# LTE.net
KiCad netlist of a schematic drawn in Altium Designer
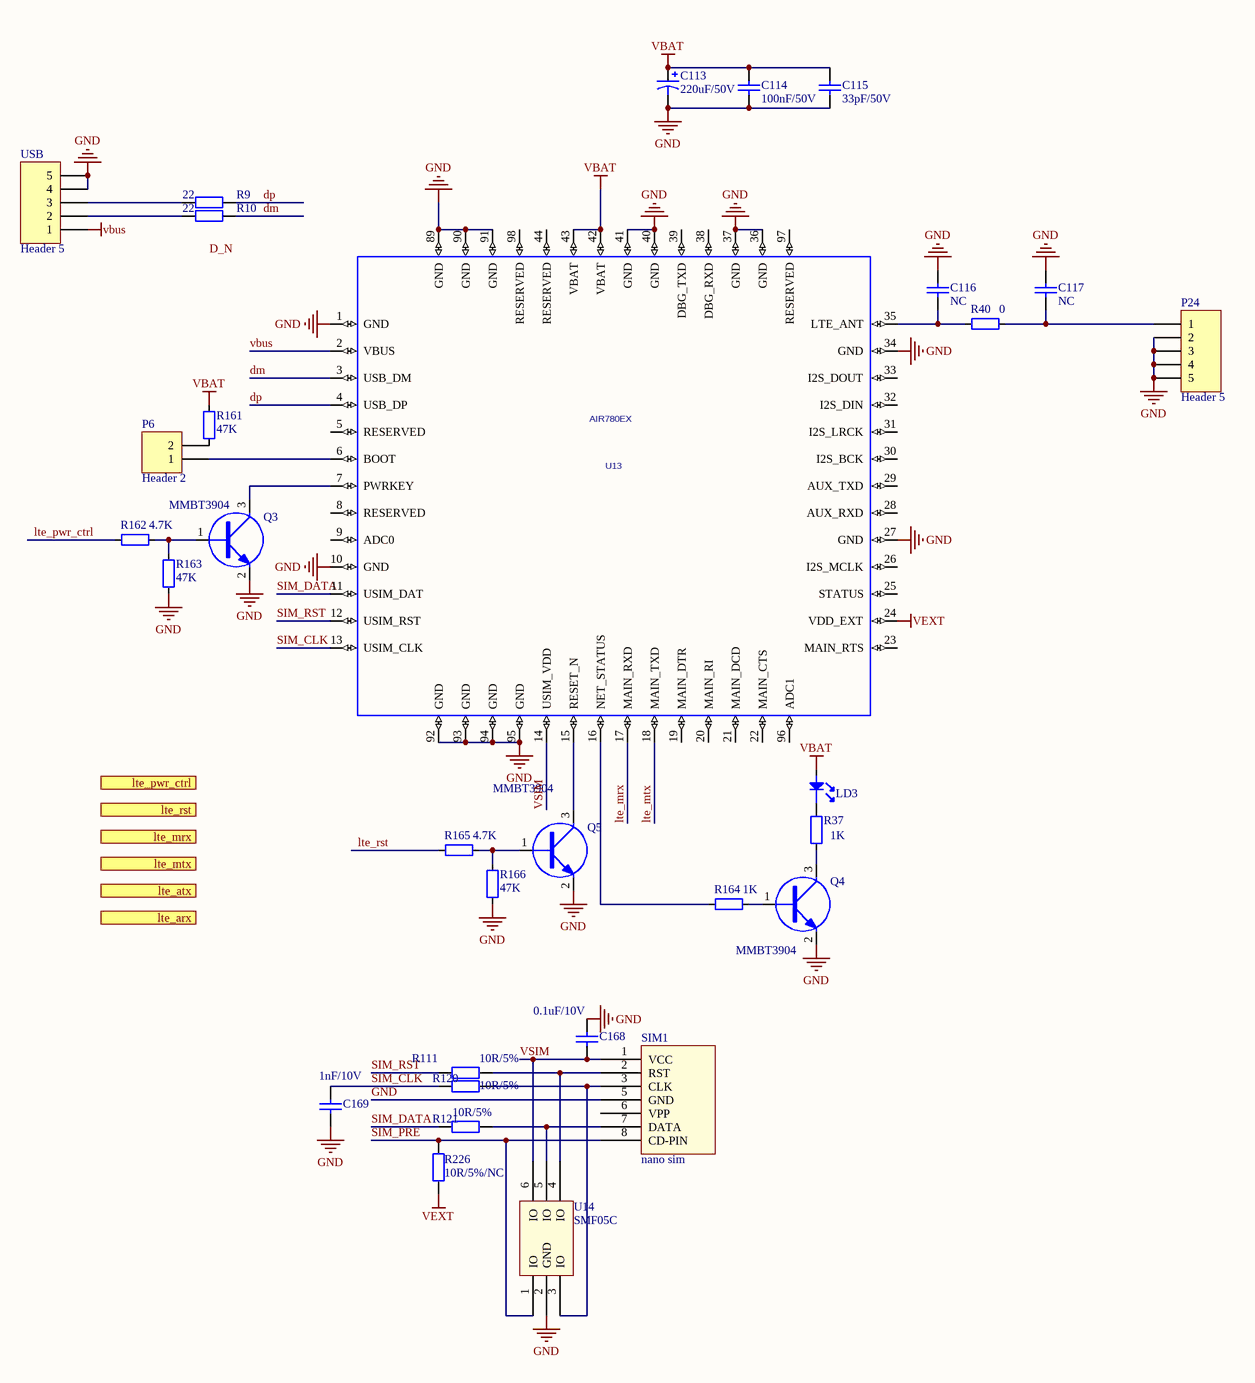
[diagram p0: LTE.SchDoc]

(export (version "E")
  (design (tool "Eeschema 10.0.6"))
  (components
    (comp (ref "C113")
      (value "220uF/50V")
      (footprint "Φ10×10")
      (description "Polarized Capacitor (Radial)")
      (fields (field (name "PUBLISHER") "Altium Limited"))
      (libsource (lib "Miscellaneous Devices") (part "Cap Pol1"))
    )
    (comp (ref "C114")
      (value "100nF/50V")
      (footprint "0603C")
      (description "Capacitor")
      (fields (field (name "PUBLISHER") "Altium Limited"))
      (libsource (lib "Miscellaneous Devices") (part "Cap"))
    )
    (comp (ref "C115")
      (value "33pF/50V")
      (footprint "0603C")
      (description "Capacitor")
      (fields (field (name "PUBLISHER") "Altium Limited"))
      (libsource (lib "Miscellaneous Devices") (part "Cap"))
    )
    (comp (ref "C116")
      (value "NC")
      (footprint "0603c")
      (description "Capacitor")
      (fields (field (name "PUBLISHER") "Altium Limited"))
      (libsource (lib "Miscellaneous Devices") (part "Cap"))
    )
    (comp (ref "C117")
      (value "NC")
      (footprint "0603c")
      (description "Capacitor")
      (fields (field (name "PUBLISHER") "Altium Limited"))
      (libsource (lib "Miscellaneous Devices") (part "Cap"))
    )
    (comp (ref "C168")
      (value "0.1uF/10V")
      (footprint "0603c")
      (description "Capacitor")
      (fields (field (name "PUBLISHER") "Altium Limited"))
      (libsource (lib "Miscellaneous Devices") (part "Cap"))
    )
    (comp (ref "C169")
      (value "1nF/10V")
      (footprint "0603c")
      (description "Capacitor")
      (fields (field (name "PUBLISHER") "Altium Limited"))
      (libsource (lib "Miscellaneous Devices") (part "Cap"))
    )
    (comp (ref "LD3")
      (value "LED_Green_19-217")
      (footprint "0603led")
      (libsource (lib "RC_M_D_00") (part "LED_Green_19-217"))
    )
    (comp (ref "P6")
      (value "Header 2")
      (footprint "HDR1X2")
      (description "Header, 2-Pin")
      (fields (field (name "PUBLISHER") "Altium Limited"))
      (libsource (lib "Miscellaneous Connectors") (part "Header 2"))
    )
    (comp (ref "P24")
      (value "Header 5")
      (footprint "KH-SMA-KE-Z")
      (description "Header, 5-Pin")
      (fields (field (name "PUBLISHER") "Altium Limited"))
      (libsource (lib "Miscellaneous Connectors") (part "Header 5"))
    )
    (comp (ref "Q3")
      (value "MMBT3904")
      (footprint "SOT23-3")
      (libsource (lib "CenLib") (part "NPN_MMBT3904"))
    )
    (comp (ref "Q4")
      (value "MMBT3904")
      (footprint "SOT23-3")
      (libsource (lib "CenLib") (part "NPN_MMBT3904"))
    )
    (comp (ref "Q5")
      (value "MMBT3904")
      (footprint "SOT23-3")
      (libsource (lib "CenLib") (part "NPN_MMBT3904"))
    )
    (comp (ref "R9")
      (value "22")
      (footprint "0402R")
      (description "Resistor SMD - IEC symbol version")
      (libsource (lib "SX1276_e266v02a") (part "Resistor"))
    )
    (comp (ref "R10")
      (value "22")
      (footprint "0402R")
      (description "Resistor SMD - IEC symbol version")
      (libsource (lib "SX1276_e266v02a") (part "Resistor"))
    )
    (comp (ref "R37") (value "1K") (footprint "0603R") (libsource (lib "RC_M_D_00") (part "RES0603")))
    (comp (ref "R40") (value "0") (footprint "0603r") (libsource (lib "RC_M_D_00") (part "RES0603")))
    (comp (ref "R111")
      (value "10R/5%")
      (footprint "0603r")
      (description "Resistor")
      (fields (field (name "PUBLISHER") "Altium Limited"))
      (libsource (lib "Miscellaneous Devices") (part "Res2"))
    )
    (comp (ref "R120")
      (value "10R/5%")
      (footprint "0603r")
      (description "Resistor")
      (fields (field (name "PUBLISHER") "Altium Limited"))
      (libsource (lib "Miscellaneous Devices") (part "Res2"))
    )
    (comp (ref "R121")
      (value "10R/5%")
      (footprint "0603r")
      (description "Resistor")
      (fields (field (name "PUBLISHER") "Altium Limited"))
      (libsource (lib "Miscellaneous Devices") (part "Res2"))
    )
    (comp (ref "R161") (value "47K") (footprint "0603r") (libsource (lib "RC_M_D_00") (part "RES0603")))
    (comp (ref "R162") (value "4.7K") (footprint "0603R") (libsource (lib "RC_M_D_00") (part "RES0603")))
    (comp (ref "R163") (value "47K") (footprint "0603r") (libsource (lib "RC_M_D_00") (part "RES0603")))
    (comp (ref "R164") (value "1K") (footprint "0603r") (libsource (lib "RC_M_D_00") (part "RES0603")))
    (comp (ref "R165") (value "4.7K") (footprint "0603R") (libsource (lib "RC_M_D_00") (part "RES0603")))
    (comp (ref "R166") (value "47K") (footprint "0603r") (libsource (lib "RC_M_D_00") (part "RES0603")))
    (comp (ref "R226")
      (value "10R/5%/NC")
      (footprint "0603r")
      (description "Resistor")
      (fields (field (name "PUBLISHER") "Altium Limited"))
      (libsource (lib "") (part "Res2_1"))
    )
    (comp (ref "SIM1") (value "nano sim") (footprint "Nano SIM") (libsource (lib "lm") (part "nano sim")))
    (comp (ref "U13")
      (value "AIR780EX")
      (footprint "Air780EX_AD:AIR780EX")
      (libsource (lib "*") (part "AIR780EX"))
    )
    (comp (ref "U14") (value "SMF05C") (footprint "sc70-6l") (libsource (lib "lm") (part "SMF05C")))
    (comp (ref "USB")
      (value "Header 5")
      (footprint "USB-MICRO-5P")
      (description "Header, 5-Pin")
      (fields (field (name "PUBLISHER") "Altium Limited"))
      (libsource (lib "") (part "Header 5_1"))
    )
  )
  (nets
    (net (code "2") (name "/SIM_CLK") (class "Default")
      (node (ref "C169") (pin "1") (pinfunction "1_1") (pintype "passive"))
      (node (ref "R120") (pin "2") (pinfunction "2_2") (pintype "passive"))
      (node (ref "U13") (pin "13") (pinfunction "USIM_CLK_13") (pintype "bidirectional"))
    )
    (net (code "3") (name "/SIM_DATA") (class "Default")
      (node (ref "R121") (pin "2") (pinfunction "2_2") (pintype "passive"))
      (node (ref "U13") (pin "11") (pinfunction "USIM_DAT_11") (pintype "bidirectional"))
    )
    (net (code "4") (name "/SIM_PRE") (class "Default")
      (node (ref "R226") (pin "1") (pinfunction "1_1") (pintype "passive"))
      (node (ref "SIM1") (pin "8") (pinfunction "CD-PIN_8") (pintype "passive"))
      (node (ref "U14") (pin "1") (pinfunction "IO_1") (pintype "passive"))
    )
    (net (code "5") (name "/SIM_RST") (class "Default")
      (node (ref "R111") (pin "2") (pinfunction "2_2") (pintype "passive"))
      (node (ref "U13") (pin "12") (pinfunction "USIM_RST_12") (pintype "bidirectional"))
    )
    (net (code "6") (name "/VSIM") (class "Default")
      (node (ref "C168") (pin "2") (pinfunction "2_2") (pintype "passive"))
      (node (ref "SIM1") (pin "1") (pinfunction "VCC_1") (pintype "passive"))
      (node (ref "U13") (pin "14") (pinfunction "USIM_VDD_14") (pintype "bidirectional"))
      (node (ref "U14") (pin "6") (pinfunction "IO_6") (pintype "passive"))
    )
    (net (code "7") (name "/dm") (class "Default")
      (node (ref "R10") (pin "2") (pinfunction "2_2") (pintype "passive"))
      (node (ref "U13") (pin "3") (pinfunction "USB_DM_3") (pintype "bidirectional"))
    )
    (net (code "8") (name "/dp") (class "Default")
      (node (ref "R9") (pin "2") (pinfunction "2_2") (pintype "passive"))
      (node (ref "U13") (pin "4") (pinfunction "USB_DP_4") (pintype "bidirectional"))
    )
    (net (code "11") (name "/lte_mrx") (class "Default")
      (node (ref "U13") (pin "17") (pinfunction "MAIN_RXD_17") (pintype "bidirectional"))
    )
    (net (code "12") (name "/lte_mtx") (class "Default")
      (node (ref "U13") (pin "18") (pinfunction "MAIN_TXD_18") (pintype "bidirectional"))
    )
    (net (code "13") (name "/lte_pwr_ctrl") (class "Default")
      (node (ref "R162") (pin "1") (pinfunction "1_1") (pintype "passive"))
    )
    (net (code "14") (name "/lte_rst") (class "Default")
      (node (ref "R165") (pin "1") (pinfunction "1_1") (pintype "passive"))
    )
    (net (code "15") (name "GND") (class "Default")
      (node (ref "C113") (pin "2") (pinfunction "2_2") (pintype "passive"))
      (node (ref "C114") (pin "1") (pinfunction "1_1") (pintype "passive"))
      (node (ref "C115") (pin "1") (pinfunction "1_1") (pintype "passive"))
      (node (ref "C116") (pin "2") (pinfunction "2_2") (pintype "passive"))
      (node (ref "C117") (pin "2") (pinfunction "2_2") (pintype "passive"))
      (node (ref "C168") (pin "1") (pinfunction "1_1") (pintype "passive"))
      (node (ref "C169") (pin "2") (pinfunction "2_2") (pintype "passive"))
      (node (ref "P24") (pin "2") (pinfunction "2_2") (pintype "passive"))
      (node (ref "P24") (pin "3") (pinfunction "3_3") (pintype "passive"))
      (node (ref "P24") (pin "4") (pinfunction "4_4") (pintype "passive"))
      (node (ref "P24") (pin "5") (pinfunction "5_5") (pintype "passive"))
      (node (ref "Q3") (pin "2") (pinfunction "E_2") (pintype "passive"))
      (node (ref "Q4") (pin "2") (pinfunction "E_2") (pintype "passive"))
      (node (ref "Q5") (pin "2") (pinfunction "E_2") (pintype "passive"))
      (node (ref "R163") (pin "1") (pinfunction "1_1") (pintype "passive"))
      (node (ref "R166") (pin "1") (pinfunction "1_1") (pintype "passive"))
      (node (ref "SIM1") (pin "5") (pinfunction "GND_5") (pintype "passive"))
      (node (ref "U13") (pin "1") (pinfunction "GND_1") (pintype "bidirectional"))
      (node (ref "U13") (pin "10") (pinfunction "GND_10") (pintype "bidirectional"))
      (node (ref "U13") (pin "27") (pinfunction "GND_27") (pintype "bidirectional"))
      (node (ref "U13") (pin "34") (pinfunction "GND_34") (pintype "bidirectional"))
      (node (ref "U13") (pin "36") (pinfunction "GND_36") (pintype "bidirectional"))
      (node (ref "U13") (pin "37") (pinfunction "GND_37") (pintype "bidirectional"))
      (node (ref "U13") (pin "40") (pinfunction "GND_40") (pintype "bidirectional"))
      (node (ref "U13") (pin "41") (pinfunction "GND_41") (pintype "bidirectional"))
      (node (ref "U13") (pin "89") (pinfunction "GND_89") (pintype "bidirectional"))
      (node (ref "U13") (pin "90") (pinfunction "GND_90") (pintype "bidirectional"))
      (node (ref "U13") (pin "91") (pinfunction "GND_91") (pintype "bidirectional"))
      (node (ref "U13") (pin "92") (pinfunction "GND_92") (pintype "bidirectional"))
      (node (ref "U13") (pin "93") (pinfunction "GND_93") (pintype "bidirectional"))
      (node (ref "U13") (pin "94") (pinfunction "GND_94") (pintype "bidirectional"))
      (node (ref "U13") (pin "95") (pinfunction "GND_95") (pintype "bidirectional"))
      (node (ref "U14") (pin "2") (pinfunction "GND_2") (pintype "passive"))
      (node (ref "USB") (pin "4") (pinfunction "4_4") (pintype "passive"))
      (node (ref "USB") (pin "5") (pinfunction "5_5") (pintype "passive"))
    )
    (net (code "16") (name "Net-(C117-Pad1)") (class "Default")
      (node (ref "C117") (pin "1") (pinfunction "1_1") (pintype "passive"))
      (node (ref "P24") (pin "1") (pinfunction "1_1") (pintype "passive"))
      (node (ref "R40") (pin "2") (pinfunction "2_2") (pintype "passive"))
    )
    (net (code "17") (name "Net-(LD3-Pad2)") (class "Default")
      (node (ref "LD3") (pin "2") (pinfunction "2_2") (pintype "passive"))
      (node (ref "R37") (pin "1") (pinfunction "1_1") (pintype "passive"))
    )
    (net (code "18") (name "Net-(P6-Pad2)") (class "Default")
      (node (ref "P6") (pin "2") (pinfunction "2_2") (pintype "passive"))
      (node (ref "R161") (pin "1") (pinfunction "1_1") (pintype "passive"))
    )
    (net (code "19") (name "Net-(Q3-B)") (class "Default")
      (node (ref "Q3") (pin "1") (pinfunction "B_1") (pintype "passive"))
      (node (ref "R162") (pin "2") (pinfunction "2_2") (pintype "passive"))
      (node (ref "R163") (pin "2") (pinfunction "2_2") (pintype "passive"))
    )
    (net (code "20") (name "Net-(Q3-C)") (class "Default")
      (node (ref "Q3") (pin "3") (pinfunction "C_3") (pintype "passive"))
      (node (ref "U13") (pin "7") (pinfunction "PWRKEY_7") (pintype "bidirectional"))
    )
    (net (code "21") (name "Net-(Q4-B)") (class "Default")
      (node (ref "Q4") (pin "1") (pinfunction "B_1") (pintype "passive"))
      (node (ref "R164") (pin "2") (pinfunction "2_2") (pintype "passive"))
    )
    (net (code "22") (name "Net-(Q4-C)") (class "Default")
      (node (ref "Q4") (pin "3") (pinfunction "C_3") (pintype "passive"))
      (node (ref "R37") (pin "2") (pinfunction "2_2") (pintype "passive"))
    )
    (net (code "23") (name "Net-(Q5-B)") (class "Default")
      (node (ref "Q5") (pin "1") (pinfunction "B_1") (pintype "passive"))
      (node (ref "R165") (pin "2") (pinfunction "2_2") (pintype "passive"))
      (node (ref "R166") (pin "2") (pinfunction "2_2") (pintype "passive"))
    )
    (net (code "24") (name "Net-(Q5-C)") (class "Default")
      (node (ref "Q5") (pin "3") (pinfunction "C_3") (pintype "passive"))
      (node (ref "U13") (pin "15") (pinfunction "RESET_N_15") (pintype "bidirectional"))
    )
    (net (code "25") (name "Net-(R9-Pad1)") (class "Default")
      (node (ref "R9") (pin "1") (pinfunction "1_1") (pintype "passive"))
      (node (ref "USB") (pin "3") (pinfunction "3_3") (pintype "passive"))
    )
    (net (code "26") (name "Net-(R10-Pad1)") (class "Default")
      (node (ref "R10") (pin "1") (pinfunction "1_1") (pintype "passive"))
      (node (ref "USB") (pin "2") (pinfunction "2_2") (pintype "passive"))
    )
    (net (code "27") (name "Net-(SIM1-CLK)") (class "Default")
      (node (ref "R120") (pin "1") (pinfunction "1_1") (pintype "passive"))
      (node (ref "SIM1") (pin "3") (pinfunction "CLK_3") (pintype "passive"))
      (node (ref "U14") (pin "3") (pinfunction "IO_3") (pintype "passive"))
    )
    (net (code "28") (name "Net-(SIM1-DATA)") (class "Default")
      (node (ref "R121") (pin "1") (pinfunction "1_1") (pintype "passive"))
      (node (ref "SIM1") (pin "7") (pinfunction "DATA_7") (pintype "passive"))
      (node (ref "U14") (pin "5") (pinfunction "IO_5") (pintype "passive"))
    )
    (net (code "29") (name "Net-(SIM1-RST)") (class "Default")
      (node (ref "R111") (pin "1") (pinfunction "1_1") (pintype "passive"))
      (node (ref "SIM1") (pin "2") (pinfunction "RST_2") (pintype "passive"))
      (node (ref "U14") (pin "4") (pinfunction "IO_4") (pintype "passive"))
    )
    (net (code "30") (name "Net-(U13-BOOT)") (class "Default")
      (node (ref "P6") (pin "1") (pinfunction "1_1") (pintype "passive"))
      (node (ref "U13") (pin "6") (pinfunction "BOOT_6") (pintype "bidirectional"))
    )
    (net (code "31") (name "Net-(U13-LTE_ANT)") (class "Default")
      (node (ref "C116") (pin "1") (pinfunction "1_1") (pintype "passive"))
      (node (ref "R40") (pin "1") (pinfunction "1_1") (pintype "passive"))
      (node (ref "U13") (pin "35") (pinfunction "LTE_ANT_35") (pintype "bidirectional"))
    )
    (net (code "32") (name "Net-(U13-NET_STATUS)") (class "Default")
      (node (ref "R164") (pin "1") (pinfunction "1_1") (pintype "passive"))
      (node (ref "U13") (pin "16") (pinfunction "NET_STATUS_16") (pintype "bidirectional"))
    )
    (net (code "33") (name "VBAT") (class "Default")
      (node (ref "C113") (pin "1") (pinfunction "1_1") (pintype "passive"))
      (node (ref "C114") (pin "2") (pinfunction "2_2") (pintype "passive"))
      (node (ref "C115") (pin "2") (pinfunction "2_2") (pintype "passive"))
      (node (ref "LD3") (pin "1") (pinfunction "1_1") (pintype "passive"))
      (node (ref "R161") (pin "2") (pinfunction "2_2") (pintype "passive"))
      (node (ref "U13") (pin "42") (pinfunction "VBAT_42") (pintype "bidirectional"))
      (node (ref "U13") (pin "43") (pinfunction "VBAT_43") (pintype "bidirectional"))
    )
    (net (code "34") (name "VEXT") (class "Default")
      (node (ref "R226") (pin "2") (pinfunction "2_2") (pintype "passive"))
      (node (ref "U13") (pin "24") (pinfunction "VDD_EXT_24") (pintype "bidirectional"))
    )
    (net (code "35") (name "unconnected-(SIM1-VPP-Pad6)") (class "Default")
      (node (ref "SIM1") (pin "6") (pinfunction "VPP_6") (pintype "passive"))
    )
    (net (code "36") (name "unconnected-(U13-ADC0-Pad9)") (class "Default")
      (node (ref "U13") (pin "9") (pinfunction "ADC0_9") (pintype "bidirectional"))
    )
    (net (code "37") (name "unconnected-(U13-ADC1-Pad96)") (class "Default")
      (node (ref "U13") (pin "96") (pinfunction "ADC1_96") (pintype "bidirectional"))
    )
    (net (code "38") (name "unconnected-(U13-AUX_RXD-Pad28)") (class "Default")
      (node (ref "U13") (pin "28") (pinfunction "AUX_RXD_28") (pintype "bidirectional"))
    )
    (net (code "39") (name "unconnected-(U13-AUX_TXD-Pad29)") (class "Default")
      (node (ref "U13") (pin "29") (pinfunction "AUX_TXD_29") (pintype "bidirectional"))
    )
    (net (code "40") (name "unconnected-(U13-DBG_RXD-Pad38)") (class "Default")
      (node (ref "U13") (pin "38") (pinfunction "DBG_RXD_38") (pintype "bidirectional"))
    )
    (net (code "41") (name "unconnected-(U13-DBG_TXD-Pad39)") (class "Default")
      (node (ref "U13") (pin "39") (pinfunction "DBG_TXD_39") (pintype "bidirectional"))
    )
    (net (code "42") (name "unconnected-(U13-I2S_BCK-Pad30)") (class "Default")
      (node (ref "U13") (pin "30") (pinfunction "I2S_BCK_30") (pintype "bidirectional"))
    )
    (net (code "43") (name "unconnected-(U13-I2S_DIN-Pad32)") (class "Default")
      (node (ref "U13") (pin "32") (pinfunction "I2S_DIN_32") (pintype "bidirectional"))
    )
    (net (code "44") (name "unconnected-(U13-I2S_DOUT-Pad33)") (class "Default")
      (node (ref "U13") (pin "33") (pinfunction "I2S_DOUT_33") (pintype "bidirectional"))
    )
    (net (code "45") (name "unconnected-(U13-I2S_LRCK-Pad31)") (class "Default")
      (node (ref "U13") (pin "31") (pinfunction "I2S_LRCK_31") (pintype "bidirectional"))
    )
    (net (code "46") (name "unconnected-(U13-I2S_MCLK-Pad26)") (class "Default")
      (node (ref "U13") (pin "26") (pinfunction "I2S_MCLK_26") (pintype "bidirectional"))
    )
    (net (code "47") (name "unconnected-(U13-MAIN_CTS-Pad22)") (class "Default")
      (node (ref "U13") (pin "22") (pinfunction "MAIN_CTS_22") (pintype "bidirectional"))
    )
    (net (code "48") (name "unconnected-(U13-MAIN_DCD-Pad21)") (class "Default")
      (node (ref "U13") (pin "21") (pinfunction "MAIN_DCD_21") (pintype "bidirectional"))
    )
    (net (code "49") (name "unconnected-(U13-MAIN_DTR-Pad19)") (class "Default")
      (node (ref "U13") (pin "19") (pinfunction "MAIN_DTR_19") (pintype "bidirectional"))
    )
    (net (code "50") (name "unconnected-(U13-MAIN_RI-Pad20)") (class "Default")
      (node (ref "U13") (pin "20") (pinfunction "MAIN_RI_20") (pintype "bidirectional"))
    )
    (net (code "51") (name "unconnected-(U13-MAIN_RTS-Pad23)") (class "Default")
      (node (ref "U13") (pin "23") (pinfunction "MAIN_RTS_23") (pintype "bidirectional"))
    )
    (net (code "52") (name "unconnected-(U13-RESERVED-Pad5)") (class "Default")
      (node (ref "U13") (pin "5") (pinfunction "RESERVED_5") (pintype "bidirectional"))
    )
    (net (code "53") (name "unconnected-(U13-RESERVED-Pad8)") (class "Default")
      (node (ref "U13") (pin "8") (pinfunction "RESERVED_8") (pintype "bidirectional"))
    )
    (net (code "54") (name "unconnected-(U13-RESERVED-Pad44)") (class "Default")
      (node (ref "U13") (pin "44") (pinfunction "RESERVED_44") (pintype "bidirectional"))
    )
    (net (code "55") (name "unconnected-(U13-RESERVED-Pad97)") (class "Default")
      (node (ref "U13") (pin "97") (pinfunction "RESERVED_97") (pintype "bidirectional"))
    )
    (net (code "56") (name "unconnected-(U13-RESERVED-Pad98)") (class "Default")
      (node (ref "U13") (pin "98") (pinfunction "RESERVED_98") (pintype "bidirectional"))
    )
    (net (code "57") (name "unconnected-(U13-STATUS-Pad25)") (class "Default")
      (node (ref "U13") (pin "25") (pinfunction "STATUS_25") (pintype "bidirectional"))
    )
    (net (code "58") (name "vbus") (class "Default")
      (node (ref "U13") (pin "2") (pinfunction "VBUS_2") (pintype "bidirectional"))
      (node (ref "USB") (pin "1") (pinfunction "1_1") (pintype "passive"))
    )
  )
)
